# controller.net
KiCad netlist of a schematic drawn in EAGLE
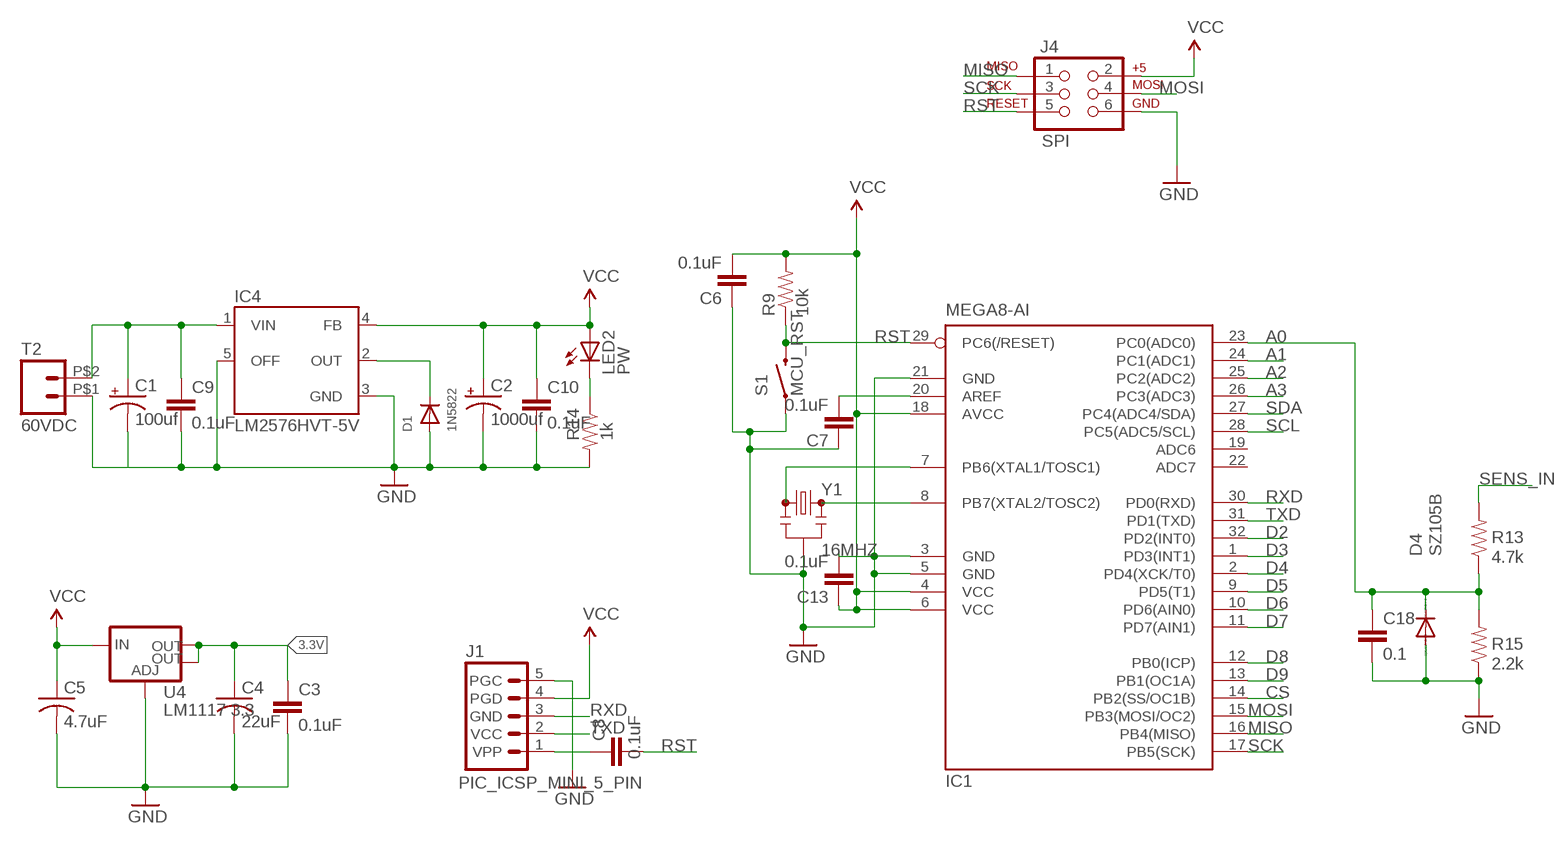
[diagram p0: schematic, sheet 1]

(export (version "E")
  (design (tool "Eeschema 10.0.6"))
  (components
    (comp (ref "C1")
      (value "100uf")
      (footprint "eagle-import:153CLV-1010")
      (libsource (lib "eagle-import") (part "CPOL-US153CLV-1010"))
    )
    (comp (ref "C2")
      (value "1000uf")
      (footprint "eagle-import:153CLV-1010")
      (libsource (lib "eagle-import") (part "CPOL-US153CLV-1010"))
    )
    (comp (ref "C3")
      (value "0.1uF")
      (footprint "eagle-import:0805")
      (libsource (lib "eagle-import") (part "CAP0805"))
    )
    (comp (ref "C4")
      (value "22uF")
      (footprint "eagle-import:C1206")
      (libsource (lib "eagle-import") (part "C-USC1206"))
    )
    (comp (ref "C5")
      (value "4.7uF")
      (footprint "eagle-import:C1206")
      (libsource (lib "eagle-import") (part "C-USC1206"))
    )
    (comp (ref "C6")
      (value "0.1uF")
      (footprint "eagle-import:0805")
      (libsource (lib "eagle-import") (part "CAP0805"))
    )
    (comp (ref "C7")
      (value "0.1uF")
      (footprint "eagle-import:0805")
      (libsource (lib "eagle-import") (part "CAP0805"))
    )
    (comp (ref "C8")
      (value "0.1uF")
      (footprint "eagle-import:0805")
      (libsource (lib "eagle-import") (part "CAP0805"))
    )
    (comp (ref "C9")
      (value "0.1uF")
      (footprint "eagle-import:0805")
      (libsource (lib "eagle-import") (part "CAP0805"))
    )
    (comp (ref "C10")
      (value "0.1uF")
      (footprint "eagle-import:0805")
      (libsource (lib "eagle-import") (part "CAP0805"))
    )
    (comp (ref "C13")
      (value "0.1uF")
      (footprint "eagle-import:0805")
      (libsource (lib "eagle-import") (part "CAP0805"))
    )
    (comp (ref "C18")
      (value "0.1")
      (footprint "eagle-import:0805")
      (libsource (lib "eagle-import") (part "CAP0805"))
    )
    (comp (ref "D1")
      (value "1N5822")
      (footprint "eagle-import:SOD-123FL")
      (libsource (lib "eagle-import") (part "DIODE_SOD-123FL"))
    )
    (comp (ref "D4")
      (value "SZ105B")
      (footprint "eagle-import:DO-214AC")
      (libsource (lib "eagle-import") (part "DIODE-DO-214AC"))
    )
    (comp (ref "IC1")
      (value "MEGA8-AI")
      (footprint "eagle-import:TQFP32-08")
      (fields (field (name "MPN") "ATMEGA8-16AU"))
      (libsource (lib "eagle-import") (part "MEGA8-AI"))
    )
    (comp (ref "IC4")
      (value "LM2576HVT-5V")
      (footprint "eagle-import:TO263-5")
      (libsource (lib "eagle-import") (part "LM2576S"))
    )
    (comp (ref "J1")
      (value "PIC_ICSP_MINI_5_PIN")
      (footprint "eagle-import:PIC_ICSP_MINI_5_PIN")
      (libsource (lib "eagle-import") (part "PIC_ICSP_MINI_5_PIN"))
    )
    (comp (ref "J4")
      (value "SPI")
      (footprint "eagle-import:2X3")
      (libsource (lib "eagle-import") (part "AVR_SPI_PRG_6PTH"))
    )
    (comp (ref "LED2")
      (value "PW")
      (footprint "eagle-import:LED3MM")
      (libsource (lib "eagle-import") (part "LED3MM"))
    )
    (comp (ref "R9")
      (value "10k")
      (footprint "eagle-import:0805")
      (libsource (lib "eagle-import") (part "RESISTOR0805-RES"))
    )
    (comp (ref "R13")
      (value "4.7k")
      (footprint "eagle-import:0805")
      (libsource (lib "eagle-import") (part "RESISTOR0805-RES"))
    )
    (comp (ref "R14")
      (value "1k")
      (footprint "eagle-import:0805")
      (libsource (lib "eagle-import") (part "RESISTOR0805-RES"))
    )
    (comp (ref "R15")
      (value "2.2k")
      (footprint "eagle-import:0805")
      (libsource (lib "eagle-import") (part "RESISTOR0805-RES"))
    )
    (comp (ref "S1")
      (value "MCU_RST")
      (footprint "eagle-import:TACTILE-SWITCH-1101NE")
      (libsource (lib "eagle-import") (part "SWITCH-MOMENTARY-2SMD-1101NE"))
    )
    (comp (ref "T2")
      (value "60VDC")
      (footprint "eagle-import:ED350V-02P")
      (libsource (lib "eagle-import") (part "ST02-3.5MM"))
    )
    (comp (ref "U4")
      (value "LM1117 3.3")
      (footprint "eagle-import:SOT223")
      (libsource (lib "eagle-import") (part "V_REG_LM1117SOT223"))
    )
    (comp (ref "Y1")
      (value "16MHZ")
      (footprint "eagle-import:RESONATOR-SMD")
      (libsource (lib "eagle-import") (part "RESONATOR16MHZ"))
    )
  )
  (nets
    (net (code "1") (name "/A0") (class "Default")
      (node (ref "C18") (pin "1") (pinfunction "1_1") (pintype "passive"))
      (node (ref "D4") (pin "C") (pinfunction "C_C") (pintype "passive"))
      (node (ref "IC1") (pin "23") (pinfunction "PC0(ADC0)_23") (pintype "bidirectional"))
      (node (ref "R13") (pin "1") (pinfunction "1_1") (pintype "passive"))
      (node (ref "R15") (pin "2") (pinfunction "2_2") (pintype "passive"))
    )
    (net (code "2") (name "/A1") (class "Default")
      (node (ref "IC1") (pin "24") (pinfunction "PC1(ADC1)_24") (pintype "bidirectional"))
    )
    (net (code "3") (name "/A2") (class "Default")
      (node (ref "IC1") (pin "25") (pinfunction "PC2(ADC2)_25") (pintype "bidirectional"))
    )
    (net (code "4") (name "/A3") (class "Default")
      (node (ref "IC1") (pin "26") (pinfunction "PC3(ADC3)_26") (pintype "bidirectional"))
    )
    (net (code "5") (name "/CS") (class "Default")
      (node (ref "IC1") (pin "14") (pinfunction "PB2(SS/OC1B)_14") (pintype "bidirectional"))
    )
    (net (code "6") (name "/D2") (class "Default")
      (node (ref "IC1") (pin "32") (pinfunction "PD2(INT0)_32") (pintype "bidirectional"))
    )
    (net (code "7") (name "/D3") (class "Default")
      (node (ref "IC1") (pin "1") (pinfunction "PD3(INT1)_1") (pintype "bidirectional"))
    )
    (net (code "8") (name "/D4") (class "Default")
      (node (ref "IC1") (pin "2") (pinfunction "PD4(XCK/T0)_2") (pintype "bidirectional"))
    )
    (net (code "9") (name "/D5") (class "Default")
      (node (ref "IC1") (pin "9") (pinfunction "PD5(T1)_9") (pintype "bidirectional"))
    )
    (net (code "10") (name "/D6") (class "Default")
      (node (ref "IC1") (pin "10") (pinfunction "PD6(AIN0)_10") (pintype "bidirectional"))
    )
    (net (code "11") (name "/D7") (class "Default")
      (node (ref "IC1") (pin "11") (pinfunction "PD7(AIN1)_11") (pintype "bidirectional"))
    )
    (net (code "12") (name "/D8") (class "Default")
      (node (ref "IC1") (pin "12") (pinfunction "PB0(ICP)_12") (pintype "bidirectional"))
    )
    (net (code "13") (name "/D9") (class "Default")
      (node (ref "IC1") (pin "13") (pinfunction "PB1(OC1A)_13") (pintype "bidirectional"))
    )
    (net (code "14") (name "/MISO") (class "Default")
      (node (ref "IC1") (pin "16") (pinfunction "PB4(MISO)_16") (pintype "bidirectional"))
      (node (ref "J4") (pin "1") (pinfunction "1_1") (pintype "passive"))
    )
    (net (code "15") (name "/MOSI") (class "Default")
      (node (ref "IC1") (pin "15") (pinfunction "PB3(MOSI/OC2)_15") (pintype "bidirectional"))
      (node (ref "J4") (pin "4") (pinfunction "4_4") (pintype "passive"))
    )
    (net (code "16") (name "/RST") (class "Default")
      (node (ref "C8") (pin "2") (pinfunction "2_2") (pintype "passive"))
      (node (ref "IC1") (pin "29") (pinfunction "PC6(/RESET)_29") (pintype "bidirectional"))
      (node (ref "J4") (pin "5") (pinfunction "5_5") (pintype "passive"))
      (node (ref "R9") (pin "1") (pinfunction "1_1") (pintype "passive"))
      (node (ref "S1") (pin "2") (pinfunction "2_2") (pintype "passive"))
    )
    (net (code "17") (name "/RXD") (class "Default")
      (node (ref "IC1") (pin "30") (pinfunction "PD0(RXD)_30") (pintype "bidirectional"))
      (node (ref "J1") (pin "3") (pinfunction "GND_3") (pintype "passive"))
    )
    (net (code "18") (name "/SCK") (class "Default")
      (node (ref "IC1") (pin "17") (pinfunction "PB5(SCK)_17") (pintype "bidirectional"))
      (node (ref "J4") (pin "3") (pinfunction "3_3") (pintype "passive"))
    )
    (net (code "19") (name "/SCL") (class "Default")
      (node (ref "IC1") (pin "28") (pinfunction "PC5(ADC5/SCL)_28") (pintype "bidirectional"))
    )
    (net (code "20") (name "/SDA") (class "Default")
      (node (ref "IC1") (pin "27") (pinfunction "PC4(ADC4/SDA)_27") (pintype "bidirectional"))
    )
    (net (code "21") (name "/SENS_IN") (class "Default")
      (node (ref "R13") (pin "2") (pinfunction "2_2") (pintype "passive"))
    )
    (net (code "22") (name "/TXD") (class "Default")
      (node (ref "IC1") (pin "31") (pinfunction "PD1(TXD)_31") (pintype "bidirectional"))
      (node (ref "J1") (pin "2") (pinfunction "VCC_2") (pintype "passive"))
    )
    (net (code "23") (name "3.3V") (class "Default")
      (node (ref "C3") (pin "1") (pinfunction "1_1") (pintype "passive"))
      (node (ref "C4") (pin "1") (pinfunction "1_1") (pintype "passive"))
      (node (ref "U4") (pin "2") (pinfunction "OUT_2") (pintype "output"))
      (node (ref "U4") (pin "4") (pinfunction "OUT_4") (pintype "output"))
    )
    (net (code "24") (name "GND") (class "Default")
      (node (ref "C1") (pin "-") (pinfunction "-_-") (pintype "passive"))
      (node (ref "C10") (pin "2") (pinfunction "2_2") (pintype "passive"))
      (node (ref "C13") (pin "2") (pinfunction "2_2") (pintype "passive"))
      (node (ref "C18") (pin "2") (pinfunction "2_2") (pintype "passive"))
      (node (ref "C2") (pin "-") (pinfunction "-_-") (pintype "passive"))
      (node (ref "C3") (pin "2") (pinfunction "2_2") (pintype "passive"))
      (node (ref "C4") (pin "2") (pinfunction "2_2") (pintype "passive"))
      (node (ref "C5") (pin "2") (pinfunction "2_2") (pintype "passive"))
      (node (ref "C6") (pin "1") (pinfunction "1_1") (pintype "passive"))
      (node (ref "C7") (pin "1") (pinfunction "1_1") (pintype "passive"))
      (node (ref "C9") (pin "2") (pinfunction "2_2") (pintype "passive"))
      (node (ref "D1") (pin "A") (pinfunction "A_A") (pintype "passive"))
      (node (ref "D4") (pin "A") (pinfunction "A_A") (pintype "passive"))
      (node (ref "IC1") (pin "21") (pinfunction "GND_21") (pintype "power_in"))
      (node (ref "IC1") (pin "3") (pinfunction "GND_3") (pintype "power_in"))
      (node (ref "IC1") (pin "5") (pinfunction "GND_5") (pintype "power_in"))
      (node (ref "IC4") (pin "3") (pinfunction "GND_3") (pintype "power_in"))
      (node (ref "IC4") (pin "5") (pinfunction "OFF_5") (pintype "input"))
      (node (ref "J1") (pin "5") (pinfunction "PGC_5") (pintype "passive"))
      (node (ref "J4") (pin "6") (pinfunction "6_6") (pintype "passive"))
      (node (ref "R14") (pin "2") (pinfunction "2_2") (pintype "passive"))
      (node (ref "R15") (pin "1") (pinfunction "1_1") (pintype "passive"))
      (node (ref "S1") (pin "1") (pinfunction "1_1") (pintype "passive"))
      (node (ref "T2") (pin "P$1") (pinfunction "1_P$1") (pintype "passive"))
      (node (ref "U4") (pin "1") (pinfunction "ADJ_1") (pintype "input"))
      (node (ref "Y1") (pin "2") (pinfunction "2_2") (pintype "passive"))
    )
    (net (code "25") (name "Net-(IC1-AREF)") (class "Default")
      (node (ref "C7") (pin "2") (pinfunction "2_2") (pintype "passive"))
      (node (ref "IC1") (pin "20") (pinfunction "AREF_20") (pintype "passive"))
    )
    (net (code "26") (name "Net-(IC1-PB6(XTAL1{slash}TOSC1))") (class "Default")
      (node (ref "IC1") (pin "7") (pinfunction "PB6(XTAL1/TOSC1)_7") (pintype "bidirectional"))
      (node (ref "Y1") (pin "1") (pinfunction "1_1") (pintype "passive"))
    )
    (net (code "27") (name "Net-(IC1-PB7(XTAL2{slash}TOSC2))") (class "Default")
      (node (ref "IC1") (pin "8") (pinfunction "PB7(XTAL2/TOSC2)_8") (pintype "bidirectional"))
      (node (ref "Y1") (pin "3") (pinfunction "3_3") (pintype "passive"))
    )
    (net (code "28") (name "Net-(IC4-OUT)") (class "Default")
      (node (ref "D1") (pin "C") (pinfunction "C_C") (pintype "passive"))
      (node (ref "IC4") (pin "2") (pinfunction "OUT_2") (pintype "output"))
    )
    (net (code "29") (name "Net-(IC4-VIN)") (class "Default")
      (node (ref "C1") (pin "+") (pinfunction "+_+") (pintype "passive"))
      (node (ref "C9") (pin "1") (pinfunction "1_1") (pintype "passive"))
      (node (ref "IC4") (pin "1") (pinfunction "VIN_1") (pintype "power_in"))
      (node (ref "T2") (pin "P$2") (pinfunction "2_P$2") (pintype "passive"))
    )
    (net (code "30") (name "Net-(J1-VPP)") (class "Default")
      (node (ref "C8") (pin "1") (pinfunction "1_1") (pintype "passive"))
      (node (ref "J1") (pin "1") (pinfunction "VPP_1") (pintype "passive"))
    )
    (net (code "31") (name "Net-(LED2-C)") (class "Default")
      (node (ref "LED2") (pin "K") (pinfunction "C_K") (pintype "passive"))
      (node (ref "R14") (pin "1") (pinfunction "1_1") (pintype "passive"))
    )
    (net (code "32") (name "VCC") (class "Default")
      (node (ref "C10") (pin "1") (pinfunction "1_1") (pintype "passive"))
      (node (ref "C13") (pin "1") (pinfunction "1_1") (pintype "passive"))
      (node (ref "C2") (pin "+") (pinfunction "+_+") (pintype "passive"))
      (node (ref "C5") (pin "1") (pinfunction "1_1") (pintype "passive"))
      (node (ref "C6") (pin "2") (pinfunction "2_2") (pintype "passive"))
      (node (ref "IC1") (pin "18") (pinfunction "AVCC_18") (pintype "power_in"))
      (node (ref "IC1") (pin "4") (pinfunction "VCC_4") (pintype "power_in"))
      (node (ref "IC1") (pin "6") (pinfunction "VCC_6") (pintype "power_in"))
      (node (ref "IC4") (pin "4") (pinfunction "FB_4") (pintype "input"))
      (node (ref "J1") (pin "4") (pinfunction "PGD_4") (pintype "passive"))
      (node (ref "J4") (pin "2") (pinfunction "2_2") (pintype "passive"))
      (node (ref "LED2") (pin "A") (pinfunction "A_A") (pintype "passive"))
      (node (ref "R9") (pin "2") (pinfunction "2_2") (pintype "passive"))
      (node (ref "U4") (pin "3") (pinfunction "IN_3") (pintype "input"))
    )
    (net (code "33") (name "unconnected-(IC1-ADC6-Pad19)") (class "Default")
      (node (ref "IC1") (pin "19") (pinfunction "ADC6_19") (pintype "bidirectional"))
    )
    (net (code "34") (name "unconnected-(IC1-ADC7-Pad22)") (class "Default")
      (node (ref "IC1") (pin "22") (pinfunction "ADC7_22") (pintype "bidirectional"))
    )
  )
)
